# STM32_with_USB-C.net
KiCad netlist of a schematic drawn in Altium Designer
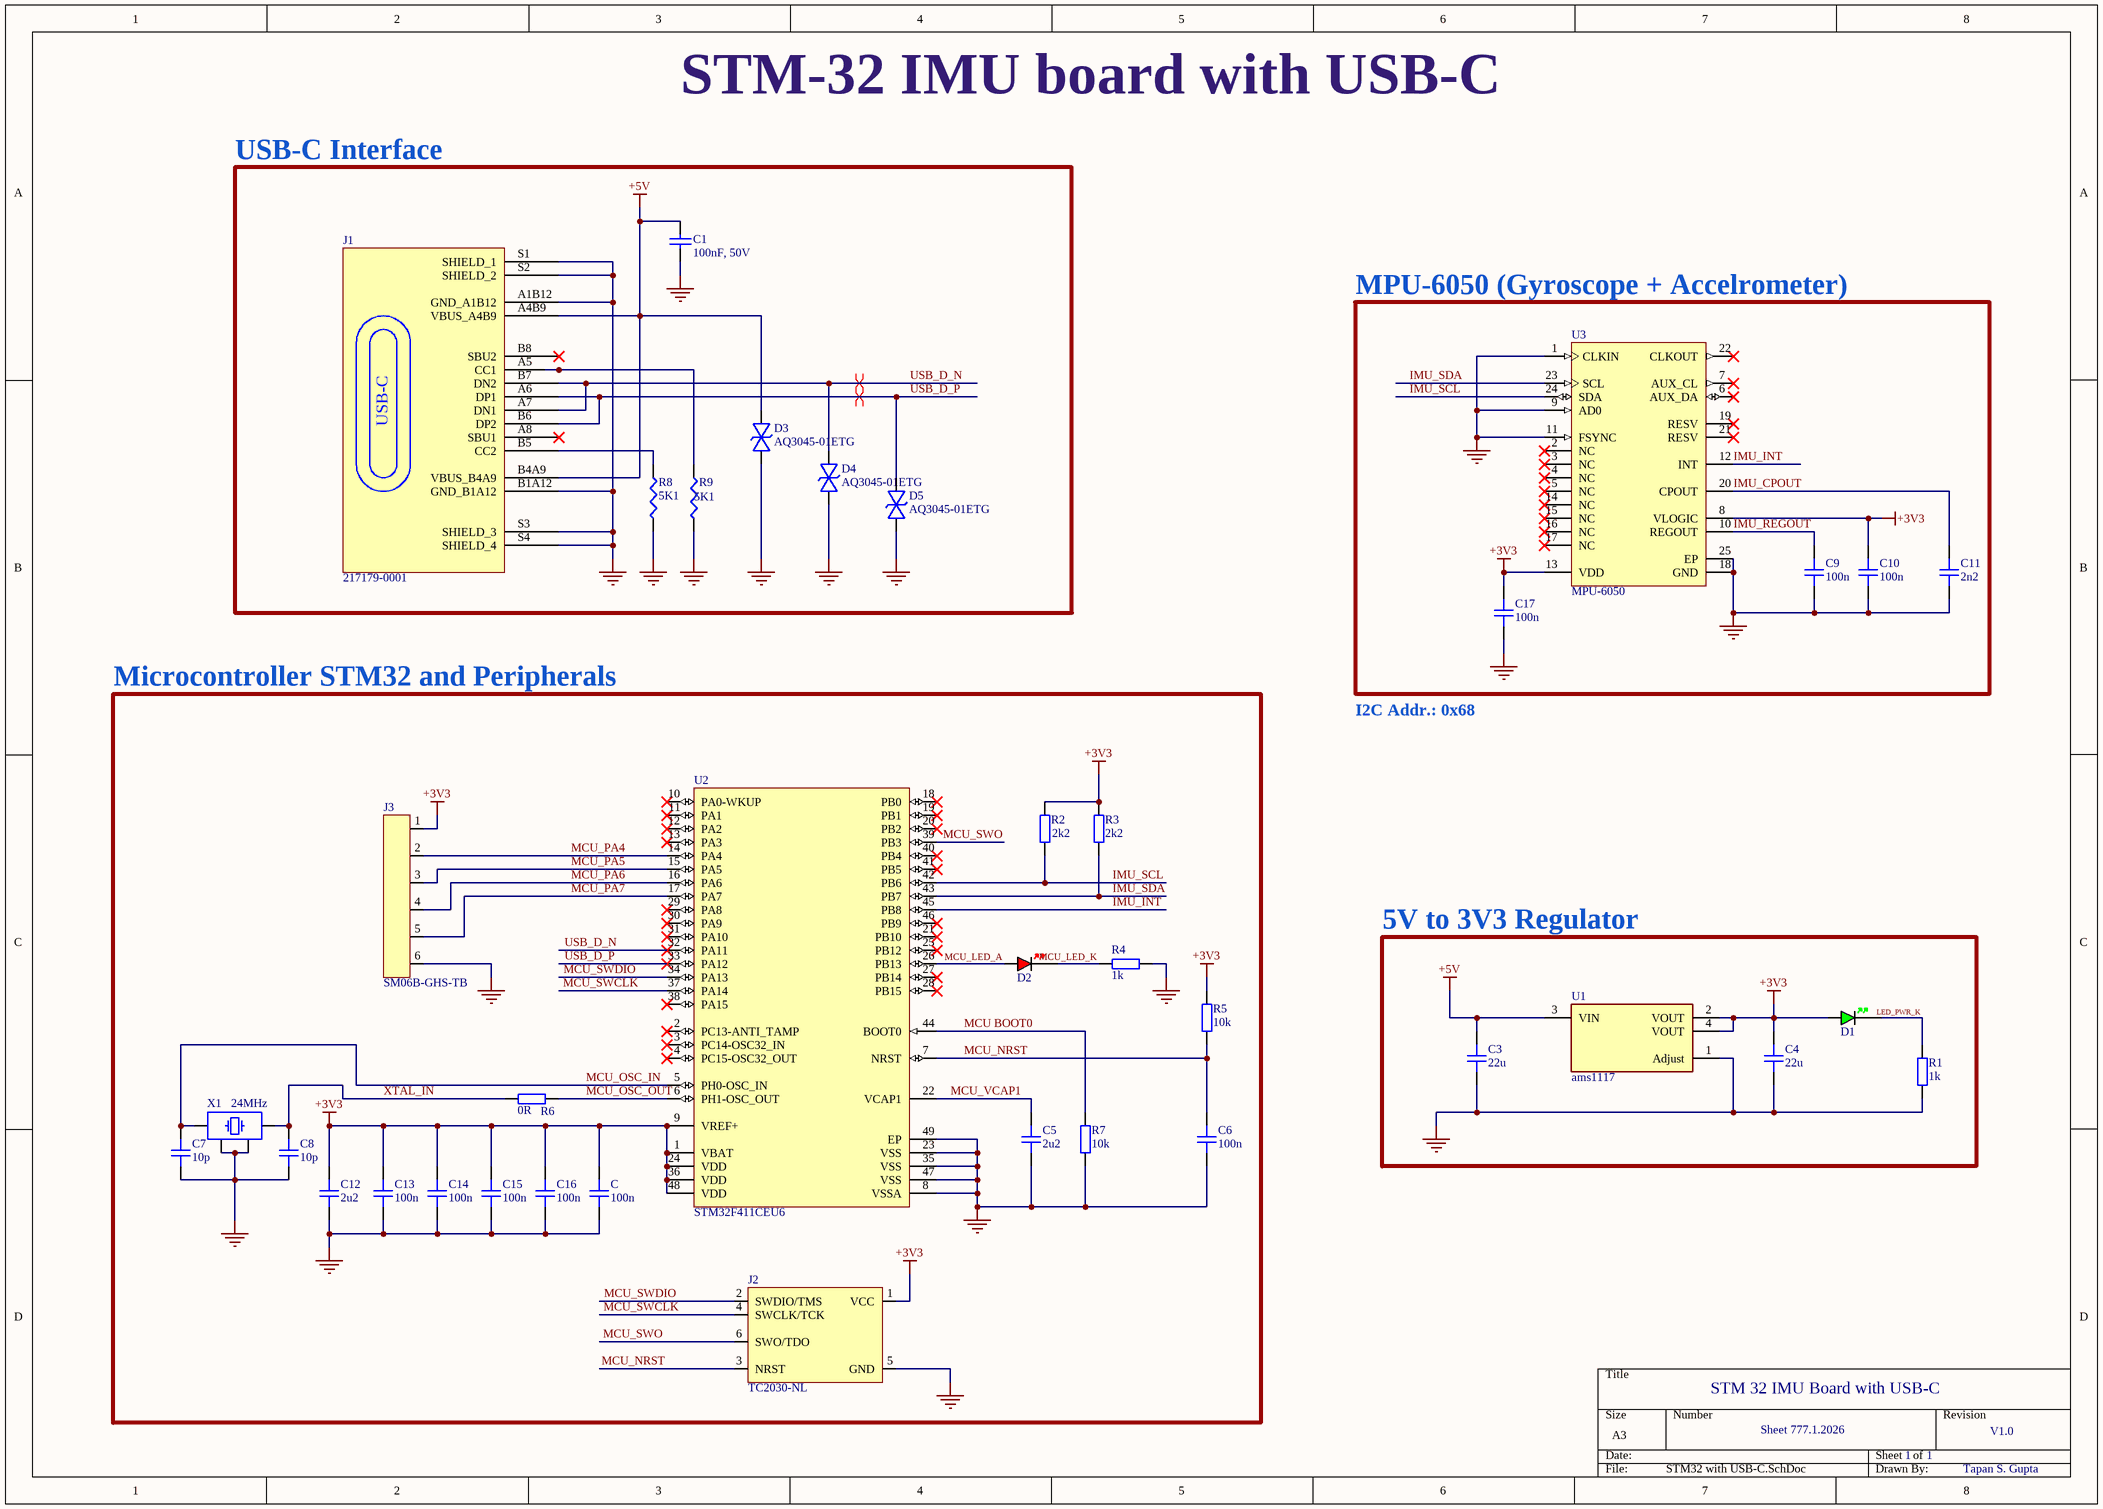
[diagram p0: STM32 with USB-C.SchDoc]

(export (version "E")
  (design (tool "Eeschema 10.0.6"))
  (components
    (comp (ref "C")
      (value "100n")
      (footprint "CAP_0402")
      (description "Capacitor SMD 0402")
      (libsource (lib "Schematic-Lib-PhilsLab") (part "CAP_0402"))
    )
    (comp (ref "C1")
      (value "100nF, 50V")
      (footprint "CAPC1005X55N")
      (description "CAP CER 0.1UF 50V X7R 0402")
      (fields
        (field (name "MANUFACTURER") "Samsung Electro-Mechanics")
        (field (name "MANUFACTURER PART NUMBER") "CL05B104KB5NNNC")
      )
      (libsource (lib "SchLIb") (part "CL05B104KB5NNNC"))
    )
    (comp (ref "C3")
      (value "22u")
      (footprint "CAP_0805")
      (description "Capacitor SMD 0805 16V")
      (libsource (lib "Schematic-Lib-PhilsLab") (part "CAP_0805"))
    )
    (comp (ref "C4")
      (value "22u")
      (footprint "CAP_0805")
      (description "Capacitor SMD 0805 16V")
      (libsource (lib "Schematic-Lib-PhilsLab") (part "CAP_0805"))
    )
    (comp (ref "C5")
      (value "2u2")
      (footprint "CAP_0603")
      (description "Capacitor SMD 0603")
      (libsource (lib "Schematic-Lib-PhilsLab") (part "CAP_0603"))
    )
    (comp (ref "C6")
      (value "100n")
      (footprint "CAP_0402")
      (description "Capacitor SMD 0402")
      (libsource (lib "Schematic-Lib-PhilsLab") (part "CAP_0402"))
    )
    (comp (ref "C7")
      (value "10p")
      (footprint "CAP_0402")
      (description "Capacitor SMD 0402 16V")
      (libsource (lib "Schematic-Lib-PhilsLab") (part "CAP_0402"))
    )
    (comp (ref "C8")
      (value "10p")
      (footprint "CAP_0402")
      (description "Capacitor SMD 0402 16V")
      (libsource (lib "Schematic-Lib-PhilsLab") (part "CAP_0402"))
    )
    (comp (ref "C9")
      (value "100n")
      (footprint "CAP_0402")
      (description "Capacitor SMD 0402 16V")
      (libsource (lib "Schematic-Lib-PhilsLab") (part "CAP_0402"))
    )
    (comp (ref "C10")
      (value "100n")
      (footprint "CAP_0402")
      (description "Capacitor SMD 0402 16V")
      (libsource (lib "Schematic-Lib-PhilsLab") (part "CAP_0402"))
    )
    (comp (ref "C11")
      (value "2n2")
      (footprint "CAP_0402")
      (description "Capacitor SMD 0402 16V")
      (libsource (lib "Schematic-Lib-PhilsLab") (part "CAP_0402"))
    )
    (comp (ref "C12")
      (value "2u2")
      (footprint "CAP_0603")
      (description "Capacitor SMD 0603")
      (libsource (lib "Schematic-Lib-PhilsLab") (part "CAP_0603"))
    )
    (comp (ref "C13")
      (value "100n")
      (footprint "CAP_0402")
      (description "Capacitor SMD 0402")
      (libsource (lib "Schematic-Lib-PhilsLab") (part "CAP_0402"))
    )
    (comp (ref "C14")
      (value "100n")
      (footprint "CAP_0402")
      (description "Capacitor SMD 0402")
      (libsource (lib "Schematic-Lib-PhilsLab") (part "CAP_0402"))
    )
    (comp (ref "C15")
      (value "100n")
      (footprint "CAP_0402")
      (description "Capacitor SMD 0402")
      (libsource (lib "Schematic-Lib-PhilsLab") (part "CAP_0402"))
    )
    (comp (ref "C16")
      (value "100n")
      (footprint "CAP_0402")
      (description "Capacitor SMD 0402")
      (libsource (lib "Schematic-Lib-PhilsLab") (part "CAP_0402"))
    )
    (comp (ref "C17")
      (value "100n")
      (footprint "CAP_0402")
      (description "Capacitor SMD 0402")
      (libsource (lib "Schematic-Lib-PhilsLab") (part "CAP_0402"))
    )
    (comp (ref "D1")
      (value "GREEN")
      (footprint "LED_0402_GREEN")
      (description "LED 0402 GREEN SMD")
      (libsource (lib "Schematic-Lib-PhilsLab") (part "LED_0402_GREEN"))
    )
    (comp (ref "D2")
      (value "RED")
      (footprint "LED_0402_RED")
      (description "LED 0402 RED SMD")
      (libsource (lib "Schematic-Lib-PhilsLab") (part "LED_0402_RED"))
    )
    (comp (ref "D3")
      (value "AQ3045-01ETG")
      (footprint "SOD882")
      (description "Bi 30Kv 5V 0.35Pf Automotve Tvs Sod882/ T&r Rohs Compliant: Yes ¦Littelfuse AQ3045-01ETG")
      (fields (field (name "MANUFACTURER") "Littelfuse"))
      (libsource (lib "SchLIb") (part "AQ3045-01ETG"))
    )
    (comp (ref "D4")
      (value "AQ3045-01ETG")
      (footprint "SOD882")
      (description "Bi 30Kv 5V 0.35Pf Automotve Tvs Sod882/ T&r Rohs Compliant: Yes ¦Littelfuse AQ3045-01ETG")
      (fields (field (name "MANUFACTURER") "Littelfuse"))
      (libsource (lib "SchLIb") (part "AQ3045-01ETG"))
    )
    (comp (ref "D5")
      (value "AQ3045-01ETG")
      (footprint "SOD882")
      (description "Bi 30Kv 5V 0.35Pf Automotve Tvs Sod882/ T&r Rohs Compliant: Yes ¦Littelfuse AQ3045-01ETG")
      (fields (field (name "MANUFACTURER") "Littelfuse"))
      (libsource (lib "SchLIb") (part "AQ3045-01ETG"))
    )
    (comp (ref "J1")
      (value "217179-0001")
      (footprint "FP-2171790001-MFG")
      (description "USB Connector, USB Type C, USB 2.0, Receptacle, 16 Ways, Surface Mount, Through Hole Mount")
      (fields (field (name "MANUFACTURER") "Molex") (field (name "LCSC PART NUMBER") "C3197684"))
      (libsource (lib "SchLIb") (part "217179-0001"))
    )
    (comp (ref "J2")
      (value "TC2030-NL")
      (footprint "TC2030-NL-FP")
      (description "Tag-Connect No-Solder SWD Debug Connector (No Legs) DO NOT PLACE")
      (fields
        (field (name "MANUFACTURER") "Tag-Connect")
        (field (name "MANUFACTURER PART NUMBER") "TC2030-NL-FP")
      )
      (libsource (lib "Schematic-Lib-PhilsLab") (part "TC2030-NL"))
    )
    (comp (ref "J3")
      (value "SM06B-GHS-TB")
      (footprint "SM06B-GHS-TB")
      (description "Header Connector 6 Position 1.25MM Pitch SMD Horizontal JST GH")
      (fields (field (name "MANUFACTURER") "JST"))
      (libsource (lib "Schematic-Lib-PhilsLab") (part "SM06B-GHS-TB"))
    )
    (comp (ref "R1")
      (value "1k")
      (footprint "RES_0402")
      (description "Resistor SMD 0402")
      (libsource (lib "Schematic-Lib-PhilsLab") (part "RES_0402"))
    )
    (comp (ref "R2")
      (value "2k2")
      (footprint "RES_0402")
      (description "Resistor SMD 0402")
      (libsource (lib "Schematic-Lib-PhilsLab") (part "RES_0402"))
    )
    (comp (ref "R3")
      (value "2k2")
      (footprint "RES_0402")
      (description "Resistor SMD 0402")
      (libsource (lib "Schematic-Lib-PhilsLab") (part "RES_0402"))
    )
    (comp (ref "R4")
      (value "1k")
      (footprint "RES_0402")
      (description "Resistor SMD 0402")
      (libsource (lib "Schematic-Lib-PhilsLab") (part "RES_0402"))
    )
    (comp (ref "R5")
      (value "10k")
      (footprint "RES_0402")
      (description "Resistor SMD 0402")
      (libsource (lib "Schematic-Lib-PhilsLab") (part "RES_0402"))
    )
    (comp (ref "R6")
      (value "0R")
      (footprint "RES_0402")
      (description "Resistor SMD 0402 0R")
      (libsource (lib "Schematic-Lib-PhilsLab") (part "RES_0402"))
    )
    (comp (ref "R7")
      (value "10k")
      (footprint "RES_0402")
      (description "Resistor SMD 0402")
      (libsource (lib "Schematic-Lib-PhilsLab") (part "RES_0402"))
    )
    (comp (ref "R8")
      (value "5K1")
      (footprint "RESC1005X37N")
      (description "Res Thick Film 0402 5.1K Ohm 1% 0.063W(1/16W) ±100ppm/C Pad SMD Automotive T/R")
      (fields
        (field (name "MANUFACTURER") "Yageo Group")
        (field (name "MANUFACTURER PART NUMBER") "AC0402FR-075K1L")
      )
      (libsource (lib "SchLIb") (part "AC0402FR-075K1L"))
    )
    (comp (ref "R9")
      (value "5K1")
      (footprint "RESC1005X37N")
      (description "Res Thick Film 0402 5.1K Ohm 1% 0.063W(1/16W) ±100ppm/C Pad SMD Automotive T/R")
      (fields
        (field (name "MANUFACTURER") "Yageo Group")
        (field (name "MANUFACTURER PART NUMBER") "AC0402FR-075K1L")
      )
      (libsource (lib "SchLIb") (part "AC0402FR-075K1L"))
    )
    (comp (ref "U1")
      (value "ams1117")
      (footprint "FP-ams1117-IPC_C")
      (description "1A LOW DROPOUT VOLTAGE REGULATOR")
      (libsource (lib "Altium Content Vault") (part "59ad430b93a2c51b3e6ee7c3b069677"))
    )
    (comp (ref "U2")
      (value "STM32F411CEU6")
      (footprint "STM-UFQFPN48_L")
      (libsource (lib "Altium Content Vault") (part "MC-ARM-STM32F411-UFQFPN48"))
    )
    (comp (ref "U3")
      (value "MPU-6050")
      (footprint "IS-QFN-24_V")
      (fields (field (name "MANUFACTURER") "InvenSense"))
      (libsource (lib "Altium Content Vault") (part "IS-MPU-6050-QFN-24"))
    )
    (comp (ref "X1")
      (value "24MHz")
      (footprint "XTAL_3225")
      (description "Crystal SMD 24MHz 10PPM 7pF 3225")
      (fields
        (field (name "MANUFACTURER") "Epson")
        (field (name "MANUFACTURER PART NUMBER") "TSX-3225 24.0000MF15X-AC")
      )
      (libsource (lib "Schematic-Lib-PhilsLab") (part "TSX-3225_24.0000MF15X-AC"))
    )
  )
  (nets
    (net (code "1") (name "+3V3") (class "Default")
      (node (ref "C") (pin "2") (pinfunction "2_2") (pintype "passive"))
      (node (ref "C10") (pin "2") (pinfunction "2_2") (pintype "passive"))
      (node (ref "C12") (pin "2") (pinfunction "2_2") (pintype "passive"))
      (node (ref "C13") (pin "2") (pinfunction "2_2") (pintype "passive"))
      (node (ref "C14") (pin "2") (pinfunction "2_2") (pintype "passive"))
      (node (ref "C15") (pin "2") (pinfunction "2_2") (pintype "passive"))
      (node (ref "C16") (pin "2") (pinfunction "2_2") (pintype "passive"))
      (node (ref "C17") (pin "2") (pinfunction "2_2") (pintype "passive"))
      (node (ref "C4") (pin "2") (pinfunction "2_2") (pintype "passive"))
      (node (ref "D1") (pin "A") (pinfunction "A_A") (pintype "passive"))
      (node (ref "J2") (pin "1") (pinfunction "VCC_1") (pintype "passive"))
      (node (ref "J3") (pin "1") (pinfunction "1_1") (pintype "passive"))
      (node (ref "R2") (pin "2") (pinfunction "2_2") (pintype "passive"))
      (node (ref "R3") (pin "2") (pinfunction "2_2") (pintype "passive"))
      (node (ref "R5") (pin "2") (pinfunction "2_2") (pintype "passive"))
      (node (ref "U1") (pin "2") (pinfunction "VOUT_2") (pintype "passive"))
      (node (ref "U1") (pin "4") (pinfunction "VOUT_4") (pintype "passive"))
      (node (ref "U2") (pin "1") (pinfunction "VBAT_1") (pintype "power_in"))
      (node (ref "U2") (pin "24") (pinfunction "VDD_24") (pintype "power_in"))
      (node (ref "U2") (pin "36") (pinfunction "VDD_36") (pintype "power_in"))
      (node (ref "U2") (pin "48") (pinfunction "VDD_48") (pintype "power_in"))
      (node (ref "U2") (pin "9") (pinfunction "VREF+_9") (pintype "power_in"))
      (node (ref "U3") (pin "13") (pinfunction "VDD_13") (pintype "power_in"))
      (node (ref "U3") (pin "8") (pinfunction "VLOGIC_8") (pintype "power_in"))
    )
    (net (code "2") (name "+5V") (class "Default")
      (node (ref "C1") (pin "2") (pinfunction "2_2") (pintype "passive"))
      (node (ref "C3") (pin "2") (pinfunction "2_2") (pintype "passive"))
      (node (ref "D3") (pin "2") (pinfunction "2_2") (pintype "passive"))
      (node (ref "J1") (pin "A4B9") (pinfunction "VBUS_A4B9_A4B9") (pintype "passive"))
      (node (ref "J1") (pin "B4A9") (pinfunction "VBUS_B4A9_B4A9") (pintype "passive"))
      (node (ref "U1") (pin "3") (pinfunction "VIN_3") (pintype "power_in"))
    )
    (net (code "3") (name "/IMU_CPOUT") (class "Default")
      (node (ref "C11") (pin "2") (pinfunction "2_2") (pintype "passive"))
      (node (ref "U3") (pin "20") (pinfunction "CPOUT_20") (pintype "passive"))
    )
    (net (code "4") (name "/IMU_INT") (class "Default")
      (node (ref "U2") (pin "45") (pinfunction "PB8_45") (pintype "bidirectional"))
      (node (ref "U3") (pin "12") (pinfunction "INT_12") (pintype "open_collector"))
    )
    (net (code "5") (name "/IMU_REGOUT") (class "Default")
      (node (ref "C9") (pin "2") (pinfunction "2_2") (pintype "passive"))
      (node (ref "U3") (pin "10") (pinfunction "REGOUT_10") (pintype "passive"))
    )
    (net (code "6") (name "/IMU_SCL") (class "Default")
      (node (ref "R2") (pin "1") (pinfunction "1_1") (pintype "passive"))
      (node (ref "U2") (pin "42") (pinfunction "PB6_42") (pintype "bidirectional"))
      (node (ref "U3") (pin "24") (pinfunction "SDA_24") (pintype "bidirectional"))
    )
    (net (code "7") (name "/IMU_SDA") (class "Default")
      (node (ref "R3") (pin "1") (pinfunction "1_1") (pintype "passive"))
      (node (ref "U2") (pin "43") (pinfunction "PB7_43") (pintype "bidirectional"))
      (node (ref "U3") (pin "23") (pinfunction "SCL_23") (pintype "input"))
    )
    (net (code "8") (name "/LED_PWR_K") (class "Default")
      (node (ref "D1") (pin "K") (pinfunction "K_K") (pintype "passive"))
      (node (ref "R1") (pin "2") (pinfunction "2_2") (pintype "passive"))
    )
    (net (code "9") (name "/MCU BOOT0") (class "Default")
      (node (ref "R7") (pin "2") (pinfunction "2_2") (pintype "passive"))
      (node (ref "U2") (pin "44") (pinfunction "BOOT0_44") (pintype "input"))
    )
    (net (code "10") (name "/MCU_LED_A") (class "Default")
      (node (ref "D2") (pin "A") (pinfunction "A_A") (pintype "passive"))
      (node (ref "U2") (pin "26") (pinfunction "PB13_26") (pintype "bidirectional"))
    )
    (net (code "11") (name "/MCU_LED_K") (class "Default")
      (node (ref "D2") (pin "K") (pinfunction "K_K") (pintype "passive"))
      (node (ref "R4") (pin "2") (pinfunction "2_2") (pintype "passive"))
    )
    (net (code "12") (name "/MCU_NRST") (class "Default")
      (node (ref "C6") (pin "2") (pinfunction "2_2") (pintype "passive"))
      (node (ref "J2") (pin "3") (pinfunction "NRST_3") (pintype "passive"))
      (node (ref "R5") (pin "1") (pinfunction "1_1") (pintype "passive"))
      (node (ref "U2") (pin "7") (pinfunction "NRST_7") (pintype "bidirectional"))
    )
    (net (code "13") (name "/MCU_OSC_IN") (class "Default")
      (node (ref "C7") (pin "2") (pinfunction "2_2") (pintype "passive"))
      (node (ref "U2") (pin "5") (pinfunction "PH0-OSC_IN_5") (pintype "bidirectional"))
      (node (ref "X1") (pin "1") (pinfunction "1_1") (pintype "passive"))
    )
    (net (code "14") (name "/MCU_OSC_OUT") (class "Default")
      (node (ref "R6") (pin "2") (pinfunction "2_2") (pintype "passive"))
      (node (ref "U2") (pin "6") (pinfunction "PH1-OSC_OUT_6") (pintype "bidirectional"))
    )
    (net (code "15") (name "/MCU_PA4") (class "Default")
      (node (ref "J3") (pin "2") (pinfunction "2_2") (pintype "passive"))
      (node (ref "U2") (pin "14") (pinfunction "PA4_14") (pintype "bidirectional"))
    )
    (net (code "16") (name "/MCU_PA5") (class "Default")
      (node (ref "J3") (pin "3") (pinfunction "3_3") (pintype "passive"))
      (node (ref "U2") (pin "15") (pinfunction "PA5_15") (pintype "bidirectional"))
    )
    (net (code "17") (name "/MCU_PA6") (class "Default")
      (node (ref "J3") (pin "4") (pinfunction "4_4") (pintype "passive"))
      (node (ref "U2") (pin "16") (pinfunction "PA6_16") (pintype "bidirectional"))
    )
    (net (code "18") (name "/MCU_PA7") (class "Default")
      (node (ref "J3") (pin "5") (pinfunction "5_5") (pintype "passive"))
      (node (ref "U2") (pin "17") (pinfunction "PA7_17") (pintype "bidirectional"))
    )
    (net (code "19") (name "/MCU_SWCLK") (class "Default")
      (node (ref "J2") (pin "4") (pinfunction "SWCLK/TCK_4") (pintype "passive"))
      (node (ref "U2") (pin "37") (pinfunction "PA14_37") (pintype "bidirectional"))
    )
    (net (code "20") (name "/MCU_SWDIO") (class "Default")
      (node (ref "J2") (pin "2") (pinfunction "SWDIO/TMS_2") (pintype "passive"))
      (node (ref "U2") (pin "34") (pinfunction "PA13_34") (pintype "bidirectional"))
    )
    (net (code "21") (name "/MCU_SWO") (class "Default")
      (node (ref "J2") (pin "6") (pinfunction "SWO/TDO_6") (pintype "passive"))
      (node (ref "U2") (pin "39") (pinfunction "PB3_39") (pintype "bidirectional"))
    )
    (net (code "22") (name "/MCU_VCAP1") (class "Default")
      (node (ref "C5") (pin "2") (pinfunction "2_2") (pintype "passive"))
      (node (ref "U2") (pin "22") (pinfunction "VCAP1_22") (pintype "passive"))
    )
    (net (code "23") (name "/USB_D_N") (class "Default")
      (node (ref "D4") (pin "2") (pinfunction "2_2") (pintype "passive"))
      (node (ref "J1") (pin "A7") (pinfunction "DN1_A7") (pintype "passive"))
      (node (ref "J1") (pin "B7") (pinfunction "DN2_B7") (pintype "passive"))
      (node (ref "U2") (pin "32") (pinfunction "PA11_32") (pintype "bidirectional"))
    )
    (net (code "24") (name "/USB_D_P") (class "Default")
      (node (ref "D5") (pin "2") (pinfunction "2_2") (pintype "passive"))
      (node (ref "J1") (pin "A6") (pinfunction "DP1_A6") (pintype "passive"))
      (node (ref "J1") (pin "B6") (pinfunction "DP2_B6") (pintype "passive"))
      (node (ref "U2") (pin "33") (pinfunction "PA12_33") (pintype "bidirectional"))
    )
    (net (code "25") (name "/XTAL_IN") (class "Default")
      (node (ref "C8") (pin "2") (pinfunction "2_2") (pintype "passive"))
      (node (ref "R6") (pin "1") (pinfunction "1_1") (pintype "passive"))
      (node (ref "X1") (pin "3") (pinfunction "3_3") (pintype "passive"))
    )
    (net (code "26") (name "GND") (class "Default")
      (node (ref "C") (pin "1") (pinfunction "1_1") (pintype "passive"))
      (node (ref "C1") (pin "1") (pinfunction "1_1") (pintype "passive"))
      (node (ref "C10") (pin "1") (pinfunction "1_1") (pintype "passive"))
      (node (ref "C11") (pin "1") (pinfunction "1_1") (pintype "passive"))
      (node (ref "C12") (pin "1") (pinfunction "1_1") (pintype "passive"))
      (node (ref "C13") (pin "1") (pinfunction "1_1") (pintype "passive"))
      (node (ref "C14") (pin "1") (pinfunction "1_1") (pintype "passive"))
      (node (ref "C15") (pin "1") (pinfunction "1_1") (pintype "passive"))
      (node (ref "C16") (pin "1") (pinfunction "1_1") (pintype "passive"))
      (node (ref "C17") (pin "1") (pinfunction "1_1") (pintype "passive"))
      (node (ref "C3") (pin "1") (pinfunction "1_1") (pintype "passive"))
      (node (ref "C4") (pin "1") (pinfunction "1_1") (pintype "passive"))
      (node (ref "C5") (pin "1") (pinfunction "1_1") (pintype "passive"))
      (node (ref "C6") (pin "1") (pinfunction "1_1") (pintype "passive"))
      (node (ref "C7") (pin "1") (pinfunction "1_1") (pintype "passive"))
      (node (ref "C8") (pin "1") (pinfunction "1_1") (pintype "passive"))
      (node (ref "C9") (pin "1") (pinfunction "1_1") (pintype "passive"))
      (node (ref "D3") (pin "1") (pinfunction "1_1") (pintype "passive"))
      (node (ref "D4") (pin "1") (pinfunction "1_1") (pintype "passive"))
      (node (ref "D5") (pin "1") (pinfunction "1_1") (pintype "passive"))
      (node (ref "J1") (pin "A1B12") (pinfunction "GND_A1B12_A1B12") (pintype "passive"))
      (node (ref "J1") (pin "B1A12") (pinfunction "GND_B1A12_B1A12") (pintype "passive"))
      (node (ref "J1") (pin "S1") (pinfunction "SHIELD_1_S1") (pintype "passive"))
      (node (ref "J1") (pin "S2") (pinfunction "SHIELD_2_S2") (pintype "passive"))
      (node (ref "J1") (pin "S3") (pinfunction "SHIELD_3_S3") (pintype "passive"))
      (node (ref "J1") (pin "S4") (pinfunction "SHIELD_4_S4") (pintype "passive"))
      (node (ref "J2") (pin "5") (pinfunction "GND_5") (pintype "passive"))
      (node (ref "J3") (pin "6") (pinfunction "6_6") (pintype "passive"))
      (node (ref "R1") (pin "1") (pinfunction "1_1") (pintype "passive"))
      (node (ref "R4") (pin "1") (pinfunction "1_1") (pintype "passive"))
      (node (ref "R7") (pin "1") (pinfunction "1_1") (pintype "passive"))
      (node (ref "R8") (pin "1") (pinfunction "1_1") (pintype "passive"))
      (node (ref "R9") (pin "1") (pinfunction "1_1") (pintype "passive"))
      (node (ref "U1") (pin "1") (pinfunction "Adjust_1") (pintype "passive"))
      (node (ref "U2") (pin "23") (pinfunction "VSS_23") (pintype "power_in"))
      (node (ref "U2") (pin "35") (pinfunction "VSS_35") (pintype "power_in"))
      (node (ref "U2") (pin "47") (pinfunction "VSS_47") (pintype "power_in"))
      (node (ref "U2") (pin "49") (pinfunction "EP_49") (pintype "power_in"))
      (node (ref "U2") (pin "8") (pinfunction "VSSA_8") (pintype "power_in"))
      (node (ref "U3") (pin "1") (pinfunction "CLKIN_1") (pintype "input"))
      (node (ref "U3") (pin "11") (pinfunction "FSYNC_11") (pintype "input"))
      (node (ref "U3") (pin "18") (pinfunction "GND_18") (pintype "power_in"))
      (node (ref "U3") (pin "25") (pinfunction "EP_25") (pintype "power_in"))
      (node (ref "U3") (pin "9") (pinfunction "AD0_9") (pintype "input"))
      (node (ref "X1") (pin "2") (pinfunction "2_2") (pintype "passive"))
      (node (ref "X1") (pin "4") (pinfunction "4_4") (pintype "passive"))
    )
    (net (code "27") (name "Net-(J1-CC1)") (class "Default")
      (node (ref "J1") (pin "A5") (pinfunction "CC1_A5") (pintype "passive"))
      (node (ref "R9") (pin "2") (pinfunction "2_2") (pintype "passive"))
    )
    (net (code "28") (name "Net-(J1-CC2)") (class "Default")
      (node (ref "J1") (pin "B5") (pinfunction "CC2_B5") (pintype "passive"))
      (node (ref "R8") (pin "2") (pinfunction "2_2") (pintype "passive"))
    )
    (net (code "29") (name "unconnected-(J1-SBU1-PadA8)") (class "Default")
      (node (ref "J1") (pin "A8") (pinfunction "SBU1_A8") (pintype "passive+no_connect"))
    )
    (net (code "30") (name "unconnected-(J1-SBU2-PadB8)") (class "Default")
      (node (ref "J1") (pin "B8") (pinfunction "SBU2_B8") (pintype "passive+no_connect"))
    )
    (net (code "31") (name "unconnected-(U2-PA0-WKUP-Pad10)") (class "Default")
      (node (ref "U2") (pin "10") (pinfunction "PA0-WKUP_10") (pintype "bidirectional+no_connect"))
    )
    (net (code "32") (name "unconnected-(U2-PA1-Pad11)") (class "Default")
      (node (ref "U2") (pin "11") (pinfunction "PA1_11") (pintype "bidirectional+no_connect"))
    )
    (net (code "33") (name "unconnected-(U2-PA2-Pad12)") (class "Default")
      (node (ref "U2") (pin "12") (pinfunction "PA2_12") (pintype "bidirectional+no_connect"))
    )
    (net (code "34") (name "unconnected-(U2-PA3-Pad13)") (class "Default")
      (node (ref "U2") (pin "13") (pinfunction "PA3_13") (pintype "bidirectional+no_connect"))
    )
    (net (code "35") (name "unconnected-(U2-PA8-Pad29)") (class "Default")
      (node (ref "U2") (pin "29") (pinfunction "PA8_29") (pintype "bidirectional+no_connect"))
    )
    (net (code "36") (name "unconnected-(U2-PA9-Pad30)") (class "Default")
      (node (ref "U2") (pin "30") (pinfunction "PA9_30") (pintype "bidirectional+no_connect"))
    )
    (net (code "37") (name "unconnected-(U2-PA10-Pad31)") (class "Default")
      (node (ref "U2") (pin "31") (pinfunction "PA10_31") (pintype "bidirectional+no_connect"))
    )
    (net (code "38") (name "unconnected-(U2-PA15-Pad38)") (class "Default")
      (node (ref "U2") (pin "38") (pinfunction "PA15_38") (pintype "bidirectional+no_connect"))
    )
    (net (code "39") (name "unconnected-(U2-PB0-Pad18)") (class "Default")
      (node (ref "U2") (pin "18") (pinfunction "PB0_18") (pintype "bidirectional+no_connect"))
    )
    (net (code "40") (name "unconnected-(U2-PB1-Pad19)") (class "Default")
      (node (ref "U2") (pin "19") (pinfunction "PB1_19") (pintype "bidirectional+no_connect"))
    )
    (net (code "41") (name "unconnected-(U2-PB2-Pad20)") (class "Default")
      (node (ref "U2") (pin "20") (pinfunction "PB2_20") (pintype "bidirectional+no_connect"))
    )
    (net (code "42") (name "unconnected-(U2-PB4-Pad40)") (class "Default")
      (node (ref "U2") (pin "40") (pinfunction "PB4_40") (pintype "bidirectional+no_connect"))
    )
    (net (code "43") (name "unconnected-(U2-PB5-Pad41)") (class "Default")
      (node (ref "U2") (pin "41") (pinfunction "PB5_41") (pintype "bidirectional+no_connect"))
    )
    (net (code "44") (name "unconnected-(U2-PB9-Pad46)") (class "Default")
      (node (ref "U2") (pin "46") (pinfunction "PB9_46") (pintype "bidirectional+no_connect"))
    )
    (net (code "45") (name "unconnected-(U2-PB10-Pad21)") (class "Default")
      (node (ref "U2") (pin "21") (pinfunction "PB10_21") (pintype "bidirectional+no_connect"))
    )
    (net (code "46") (name "unconnected-(U2-PB12-Pad25)") (class "Default")
      (node (ref "U2") (pin "25") (pinfunction "PB12_25") (pintype "bidirectional+no_connect"))
    )
    (net (code "47") (name "unconnected-(U2-PB14-Pad27)") (class "Default")
      (node (ref "U2") (pin "27") (pinfunction "PB14_27") (pintype "bidirectional+no_connect"))
    )
    (net (code "48") (name "unconnected-(U2-PB15-Pad28)") (class "Default")
      (node (ref "U2") (pin "28") (pinfunction "PB15_28") (pintype "bidirectional+no_connect"))
    )
    (net (code "49") (name "unconnected-(U2-PC13-ANTI_TAMP-Pad2)") (class "Default")
      (node (ref "U2") (pin "2") (pinfunction "PC13-ANTI_TAMP_2") (pintype "bidirectional+no_connect"))
    )
    (net (code "50") (name "unconnected-(U2-PC14-OSC32_IN-Pad3)") (class "Default")
      (node (ref "U2") (pin "3") (pinfunction "PC14-OSC32_IN_3") (pintype "bidirectional+no_connect"))
    )
    (net (code "51") (name "unconnected-(U2-PC15-OSC32_OUT-Pad4)") (class "Default")
      (node (ref "U2") (pin "4") (pinfunction "PC15-OSC32_OUT_4") (pintype "bidirectional+no_connect"))
    )
    (net (code "52") (name "unconnected-(U3-AUX_CL-Pad7)") (class "Default")
      (node (ref "U3") (pin "7") (pinfunction "AUX_CL_7") (pintype "output+no_connect"))
    )
    (net (code "53") (name "unconnected-(U3-AUX_DA-Pad6)") (class "Default")
      (node (ref "U3") (pin "6") (pinfunction "AUX_DA_6") (pintype "bidirectional+no_connect"))
    )
    (net (code "54") (name "unconnected-(U3-CLKOUT-Pad22)") (class "Default")
      (node (ref "U3") (pin "22") (pinfunction "CLKOUT_22") (pintype "output+no_connect"))
    )
    (net (code "55") (name "unconnected-(U3-NC-Pad2)") (class "Default")
      (node (ref "U3") (pin "2") (pinfunction "NC_2") (pintype "passive+no_connect"))
    )
    (net (code "56") (name "unconnected-(U3-NC-Pad3)") (class "Default")
      (node (ref "U3") (pin "3") (pinfunction "NC_3") (pintype "passive+no_connect"))
    )
    (net (code "57") (name "unconnected-(U3-NC-Pad4)") (class "Default")
      (node (ref "U3") (pin "4") (pinfunction "NC_4") (pintype "passive+no_connect"))
    )
    (net (code "58") (name "unconnected-(U3-NC-Pad5)") (class "Default")
      (node (ref "U3") (pin "5") (pinfunction "NC_5") (pintype "passive+no_connect"))
    )
    (net (code "59") (name "unconnected-(U3-NC-Pad14)") (class "Default")
      (node (ref "U3") (pin "14") (pinfunction "NC_14") (pintype "passive+no_connect"))
    )
    (net (code "60") (name "unconnected-(U3-NC-Pad15)") (class "Default")
      (node (ref "U3") (pin "15") (pinfunction "NC_15") (pintype "passive+no_connect"))
    )
    (net (code "61") (name "unconnected-(U3-NC-Pad16)") (class "Default")
      (node (ref "U3") (pin "16") (pinfunction "NC_16") (pintype "passive+no_connect"))
    )
    (net (code "62") (name "unconnected-(U3-NC-Pad17)") (class "Default")
      (node (ref "U3") (pin "17") (pinfunction "NC_17") (pintype "passive+no_connect"))
    )
    (net (code "63") (name "unconnected-(U3-RESV-Pad19)") (class "Default")
      (node (ref "U3") (pin "19") (pinfunction "RESV_19") (pintype "passive+no_connect"))
    )
    (net (code "64") (name "unconnected-(U3-RESV-Pad21)") (class "Default")
      (node (ref "U3") (pin "21") (pinfunction "RESV_21") (pintype "passive+no_connect"))
    )
  )
)
